# FMBTECH.net
KiCad netlist of a schematic drawn in EAGLE
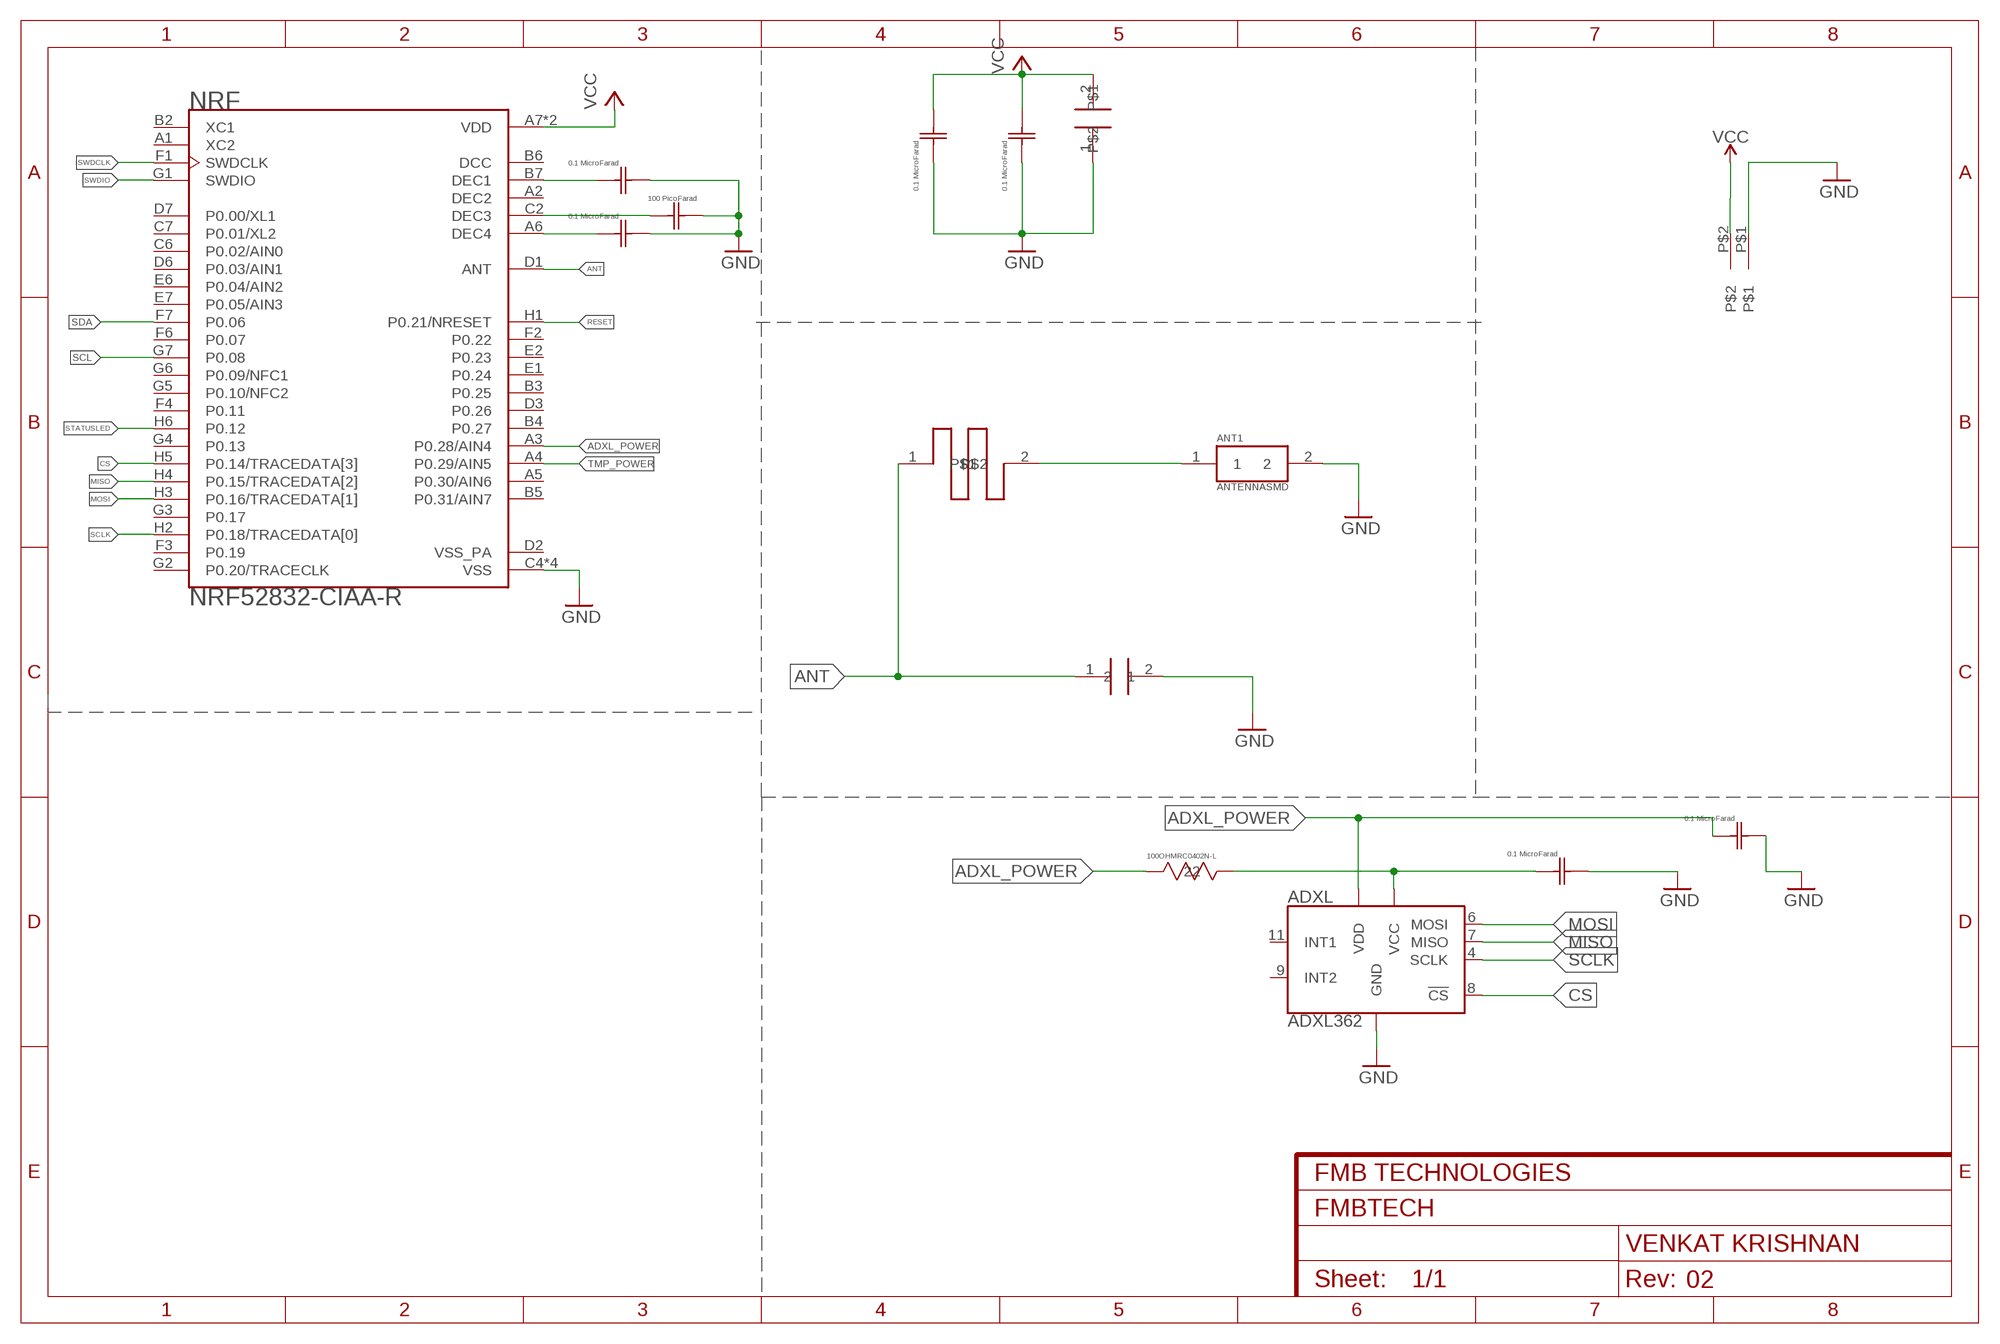
[diagram p0: schematic, sheet 1]

(export (version "E")
  (design (tool "Eeschema 10.0.6"))
  (components
    (comp (ref "ADXL")
      (value "ADXL362")
      (footprint "eagle-import:TFLGA-16_3.3MMX3.1MM")
      (fields (field (name "MF") "Analog Devices") (field (name "MP") "ADXL362BCCZ-RL7"))
      (libsource (lib "eagle-import") (part "ADXL362"))
    )
    (comp (ref "ANT1")
      (value "ANTENNASMD")
      (footprint "eagle-import:1")
      (fields (field (name "MF") "Pulse") (field (name "MP") "W3008"))
      (libsource (lib "eagle-import") (part "ANTENNASMD"))
    )
    (comp (ref "C1")
      (value "02016D104KAT2A")
      (footprint "eagle-import:0201")
      (libsource (lib "eagle-import") (part "02016D104KAT2A"))
    )
    (comp (ref "C2")
      (value "02016D104KAT2A")
      (footprint "eagle-import:0201")
      (libsource (lib "eagle-import") (part "02016D104KAT2A"))
    )
    (comp (ref "C3")
      (value "GRM0335C1E101JA01D")
      (footprint "eagle-import:G-033")
      (libsource (lib "eagle-import") (part "GRM0335C1E101JA01D"))
    )
    (comp (ref "C6")
      (value "02016D104KAT2A")
      (footprint "eagle-import:0201")
      (libsource (lib "eagle-import") (part "02016D104KAT2A"))
    )
    (comp (ref "C7")
      (value "02016D104KAT2A")
      (footprint "eagle-import:0201")
      (libsource (lib "eagle-import") (part "02016D104KAT2A"))
    )
    (comp (ref "C8")
      (value "02016D104KAT2A")
      (footprint "eagle-import:0201")
      (libsource (lib "eagle-import") (part "02016D104KAT2A"))
    )
    (comp (ref "C9")
      (value "02016D104KAT2A")
      (footprint "eagle-import:0201")
      (libsource (lib "eagle-import") (part "02016D104KAT2A"))
    )
    (comp (ref "NRF")
      (value "NRF52832-CIAA-R")
      (footprint "eagle-import:BGA50N40P7X8_300X320X40")
      (fields (field (name "MF") "Nordic Semiconductor"))
      (libsource (lib "eagle-import") (part "NRF52832-CIAA-R"))
    )
    (comp (ref "R6")
      (value "100OHMRC0402N-L")
      (footprint "eagle-import:RES")
      (fields (field (name "MANUFACTURER_PART_NUMBER") "RC0402FR07100RL"))
      (libsource (lib "eagle-import") (part "100OHMRC0402N-L"))
    )
    (comp (ref "U$1")
      (value "4.7µF")
      (footprint "eagle-import:CAP")
      (libsource (lib "eagle-import") (part "4.7µF"))
    )
    (comp (ref "U$2")
      (value "0.8PF")
      (footprint "eagle-import:CAP")
      (libsource (lib "eagle-import") (part "0.8PF"))
    )
    (comp (ref "U$3")
      (value "INDUCTOR")
      (footprint "eagle-import:1")
      (libsource (lib "eagle-import") (part "INDUCTOR"))
    )
    (comp (ref "U$4")
      (value "SUPPLY")
      (footprint "eagle-import:SUPPLY")
      (libsource (lib "eagle-import") (part "SUPPLY"))
    )
  )
  (nets
    (net (code "1") (name "/DCC") (class "Default")
      (node (ref "NRF") (pin "B6") (pinfunction "DCC_B6") (pintype "power_in"))
    )
    (net (code "2") (name "/DEC2") (class "Default")
      (node (ref "NRF") (pin "A2") (pinfunction "DEC2_A2") (pintype "power_in"))
    )
    (net (code "3") (name "/VSS_PA") (class "Default")
      (node (ref "NRF") (pin "D2") (pinfunction "VSS_PA_D2") (pintype "power_in"))
    )
    (net (code "4") (name "ADXL_POWER") (class "Default")
      (node (ref "ADXL") (pin "1") (pinfunction "VDD_1") (pintype "bidirectional"))
      (node (ref "C9") (pin "1") (pinfunction "1_1") (pintype "passive"))
      (node (ref "NRF") (pin "A3") (pinfunction "P0.28/AIN4_A3") (pintype "bidirectional"))
      (node (ref "R6") (pin "1") (pinfunction "11_1") (pintype "passive"))
    )
    (net (code "5") (name "ANT") (class "Default")
      (node (ref "NRF") (pin "D1") (pinfunction "ANT_D1") (pintype "passive"))
      (node (ref "U$2") (pin "1") (pinfunction "1_1") (pintype "bidirectional"))
      (node (ref "U$3") (pin "1") (pinfunction "P$1_1") (pintype "bidirectional"))
    )
    (net (code "6") (name "CS") (class "Default")
      (node (ref "ADXL") (pin "8") (pinfunction "~{CS}_8") (pintype "bidirectional"))
      (node (ref "NRF") (pin "H5") (pinfunction "P0.14/TRACEDATA[3]_H5") (pintype "bidirectional"))
    )
    (net (code "7") (name "GND") (class "Default")
      (node (ref "ADXL") (pin "12") (pinfunction "GND_12") (pintype "bidirectional"))
      (node (ref "ADXL") (pin "13") (pinfunction "GND_13") (pintype "bidirectional"))
      (node (ref "ADXL") (pin "16") (pinfunction "GND_16") (pintype "bidirectional"))
      (node (ref "ANT1") (pin "2") (pinfunction "2_2") (pintype "passive"))
      (node (ref "C1") (pin "2") (pinfunction "2_2") (pintype "passive"))
      (node (ref "C2") (pin "2") (pinfunction "2_2") (pintype "passive"))
      (node (ref "C3") (pin "2") (pinfunction "22_2") (pintype "passive"))
      (node (ref "C6") (pin "1") (pinfunction "1_1") (pintype "passive"))
      (node (ref "C7") (pin "1") (pinfunction "1_1") (pintype "passive"))
      (node (ref "C8") (pin "2") (pinfunction "2_2") (pintype "passive"))
      (node (ref "C9") (pin "2") (pinfunction "2_2") (pintype "passive"))
      (node (ref "NRF") (pin "C4") (pinfunction "VSS_C4") (pintype "power_in"))
      (node (ref "NRF") (pin "C5") (pinfunction "VSS_C5") (pintype "power_in"))
      (node (ref "NRF") (pin "E3") (pinfunction "VSS_E3") (pintype "power_in"))
      (node (ref "NRF") (pin "F5") (pinfunction "VSS_F5") (pintype "power_in"))
      (node (ref "U$1") (pin "1") (pinfunction "P$1_1") (pintype "bidirectional"))
      (node (ref "U$2") (pin "2") (pinfunction "2_2") (pintype "bidirectional"))
      (node (ref "U$4") (pin "P$1") (pinfunction "P$1_P$1") (pintype "bidirectional"))
    )
    (net (code "8") (name "MISO") (class "Default")
      (node (ref "ADXL") (pin "7") (pinfunction "MISO_7") (pintype "bidirectional"))
      (node (ref "NRF") (pin "H4") (pinfunction "P0.15/TRACEDATA[2]_H4") (pintype "bidirectional"))
    )
    (net (code "9") (name "MOSI") (class "Default")
      (node (ref "ADXL") (pin "6") (pinfunction "MOSI_6") (pintype "bidirectional"))
      (node (ref "NRF") (pin "H3") (pinfunction "P0.16/TRACEDATA[1]_H3") (pintype "bidirectional"))
    )
    (net (code "10") (name "Net-(ADXL-VCC)") (class "Default")
      (node (ref "ADXL") (pin "14") (pinfunction "VCC_14") (pintype "bidirectional"))
      (node (ref "C8") (pin "1") (pinfunction "1_1") (pintype "passive"))
      (node (ref "R6") (pin "2") (pinfunction "22_2") (pintype "passive"))
    )
    (net (code "11") (name "Net-(C3-11)") (class "Default")
      (node (ref "C3") (pin "1") (pinfunction "11_1") (pintype "passive"))
      (node (ref "NRF") (pin "C2") (pinfunction "DEC3_C2") (pintype "power_in"))
    )
    (net (code "12") (name "Net-(NRF-DEC1)") (class "Default")
      (node (ref "C1") (pin "1") (pinfunction "1_1") (pintype "passive"))
      (node (ref "NRF") (pin "B7") (pinfunction "DEC1_B7") (pintype "power_in"))
    )
    (net (code "13") (name "Net-(NRF-DEC4)") (class "Default")
      (node (ref "C2") (pin "1") (pinfunction "1_1") (pintype "passive"))
      (node (ref "NRF") (pin "A6") (pinfunction "DEC4_A6") (pintype "power_in"))
    )
    (net (code "14") (name "Net-(U$3-P$2)") (class "Default")
      (node (ref "ANT1") (pin "1") (pinfunction "1_1") (pintype "passive"))
      (node (ref "U$3") (pin "2") (pinfunction "P$2_2") (pintype "bidirectional"))
    )
    (net (code "15") (name "RESET") (class "Default")
      (node (ref "NRF") (pin "H1") (pinfunction "P0.21/NRESET_H1") (pintype "bidirectional"))
    )
    (net (code "16") (name "SCL") (class "Default")
      (node (ref "NRF") (pin "G7") (pinfunction "P0.08_G7") (pintype "bidirectional"))
    )
    (net (code "17") (name "SCLK") (class "Default")
      (node (ref "ADXL") (pin "4") (pinfunction "SCLK_4") (pintype "bidirectional"))
      (node (ref "NRF") (pin "H2") (pinfunction "P0.18/TRACEDATA[0]_H2") (pintype "bidirectional"))
    )
    (net (code "18") (name "SDA") (class "Default")
      (node (ref "NRF") (pin "F7") (pinfunction "P0.06_F7") (pintype "bidirectional"))
    )
    (net (code "19") (name "STATUSLED") (class "Default")
      (node (ref "NRF") (pin "H6") (pinfunction "P0.12_H6") (pintype "bidirectional"))
    )
    (net (code "20") (name "SWDCLK") (class "Default")
      (node (ref "NRF") (pin "F1") (pinfunction "SWDCLK_F1") (pintype "input"))
    )
    (net (code "21") (name "SWDIO") (class "Default")
      (node (ref "NRF") (pin "G1") (pinfunction "SWDIO_G1") (pintype "bidirectional"))
    )
    (net (code "22") (name "TMP_POWER") (class "Default")
      (node (ref "NRF") (pin "A4") (pinfunction "P0.29/AIN5_A4") (pintype "bidirectional"))
    )
    (net (code "23") (name "VCC") (class "Default")
      (node (ref "C6") (pin "2") (pinfunction "2_2") (pintype "passive"))
      (node (ref "C7") (pin "2") (pinfunction "2_2") (pintype "passive"))
      (node (ref "NRF") (pin "A7") (pinfunction "VDD_A7") (pintype "power_in"))
      (node (ref "NRF") (pin "H7") (pinfunction "VDD_H7") (pintype "power_in"))
      (node (ref "U$1") (pin "2") (pinfunction "P$2_2") (pintype "bidirectional"))
      (node (ref "U$4") (pin "P$2") (pinfunction "P$2_P$2") (pintype "bidirectional"))
    )
    (net (code "24") (name "unconnected-(ADXL-INT1-Pad11)") (class "Default")
      (node (ref "ADXL") (pin "11") (pinfunction "INT1_11") (pintype "bidirectional"))
    )
    (net (code "25") (name "unconnected-(ADXL-INT2-Pad9)") (class "Default")
      (node (ref "ADXL") (pin "9") (pinfunction "INT2_9") (pintype "bidirectional"))
    )
    (net (code "26") (name "unconnected-(NRF-P0.00{slash}XL1-PadD7)") (class "Default")
      (node (ref "NRF") (pin "D7") (pinfunction "P0.00/XL1_D7") (pintype "bidirectional"))
    )
    (net (code "27") (name "unconnected-(NRF-P0.01{slash}XL2-PadC7)") (class "Default")
      (node (ref "NRF") (pin "C7") (pinfunction "P0.01/XL2_C7") (pintype "bidirectional"))
    )
    (net (code "28") (name "unconnected-(NRF-P0.02{slash}AIN0-PadC6)") (class "Default")
      (node (ref "NRF") (pin "C6") (pinfunction "P0.02/AIN0_C6") (pintype "bidirectional"))
    )
    (net (code "29") (name "unconnected-(NRF-P0.03{slash}AIN1-PadD6)") (class "Default")
      (node (ref "NRF") (pin "D6") (pinfunction "P0.03/AIN1_D6") (pintype "bidirectional"))
    )
    (net (code "30") (name "unconnected-(NRF-P0.04{slash}AIN2-PadE6)") (class "Default")
      (node (ref "NRF") (pin "E6") (pinfunction "P0.04/AIN2_E6") (pintype "bidirectional"))
    )
    (net (code "31") (name "unconnected-(NRF-P0.05{slash}AIN3-PadE7)") (class "Default")
      (node (ref "NRF") (pin "E7") (pinfunction "P0.05/AIN3_E7") (pintype "bidirectional"))
    )
    (net (code "32") (name "unconnected-(NRF-P0.07-PadF6)") (class "Default")
      (node (ref "NRF") (pin "F6") (pinfunction "P0.07_F6") (pintype "bidirectional"))
    )
    (net (code "33") (name "unconnected-(NRF-P0.09{slash}NFC1-PadG6)") (class "Default")
      (node (ref "NRF") (pin "G6") (pinfunction "P0.09/NFC1_G6") (pintype "bidirectional"))
    )
    (net (code "34") (name "unconnected-(NRF-P0.10{slash}NFC2-PadG5)") (class "Default")
      (node (ref "NRF") (pin "G5") (pinfunction "P0.10/NFC2_G5") (pintype "bidirectional"))
    )
    (net (code "35") (name "unconnected-(NRF-P0.11-PadF4)") (class "Default")
      (node (ref "NRF") (pin "F4") (pinfunction "P0.11_F4") (pintype "bidirectional"))
    )
    (net (code "36") (name "unconnected-(NRF-P0.13-PadG4)") (class "Default")
      (node (ref "NRF") (pin "G4") (pinfunction "P0.13_G4") (pintype "bidirectional"))
    )
    (net (code "37") (name "unconnected-(NRF-P0.17-PadG3)") (class "Default")
      (node (ref "NRF") (pin "G3") (pinfunction "P0.17_G3") (pintype "bidirectional"))
    )
    (net (code "38") (name "unconnected-(NRF-P0.19-PadF3)") (class "Default")
      (node (ref "NRF") (pin "F3") (pinfunction "P0.19_F3") (pintype "bidirectional"))
    )
    (net (code "39") (name "unconnected-(NRF-P0.20{slash}TRACECLK-PadG2)") (class "Default")
      (node (ref "NRF") (pin "G2") (pinfunction "P0.20/TRACECLK_G2") (pintype "bidirectional"))
    )
    (net (code "40") (name "unconnected-(NRF-P0.22-PadF2)") (class "Default")
      (node (ref "NRF") (pin "F2") (pinfunction "P0.22_F2") (pintype "bidirectional"))
    )
    (net (code "41") (name "unconnected-(NRF-P0.23-PadE2)") (class "Default")
      (node (ref "NRF") (pin "E2") (pinfunction "P0.23_E2") (pintype "bidirectional"))
    )
    (net (code "42") (name "unconnected-(NRF-P0.24-PadE1)") (class "Default")
      (node (ref "NRF") (pin "E1") (pinfunction "P0.24_E1") (pintype "bidirectional"))
    )
    (net (code "43") (name "unconnected-(NRF-P0.25-PadB3)") (class "Default")
      (node (ref "NRF") (pin "B3") (pinfunction "P0.25_B3") (pintype "bidirectional"))
    )
    (net (code "44") (name "unconnected-(NRF-P0.26-PadD3)") (class "Default")
      (node (ref "NRF") (pin "D3") (pinfunction "P0.26_D3") (pintype "bidirectional"))
    )
    (net (code "45") (name "unconnected-(NRF-P0.27-PadB4)") (class "Default")
      (node (ref "NRF") (pin "B4") (pinfunction "P0.27_B4") (pintype "bidirectional"))
    )
    (net (code "46") (name "unconnected-(NRF-P0.30{slash}AIN6-PadA5)") (class "Default")
      (node (ref "NRF") (pin "A5") (pinfunction "P0.30/AIN6_A5") (pintype "bidirectional"))
    )
    (net (code "47") (name "unconnected-(NRF-P0.31{slash}AIN7-PadB5)") (class "Default")
      (node (ref "NRF") (pin "B5") (pinfunction "P0.31/AIN7_B5") (pintype "bidirectional"))
    )
    (net (code "48") (name "unconnected-(NRF-XC1-PadB2)") (class "Default")
      (node (ref "NRF") (pin "B2") (pinfunction "XC1_B2") (pintype "input"))
    )
    (net (code "49") (name "unconnected-(NRF-XC2-PadA1)") (class "Default")
      (node (ref "NRF") (pin "A1") (pinfunction "XC2_A1") (pintype "input"))
    )
  )
)
